# EpromEmu.net
KiCad netlist of a schematic drawn in EAGLE
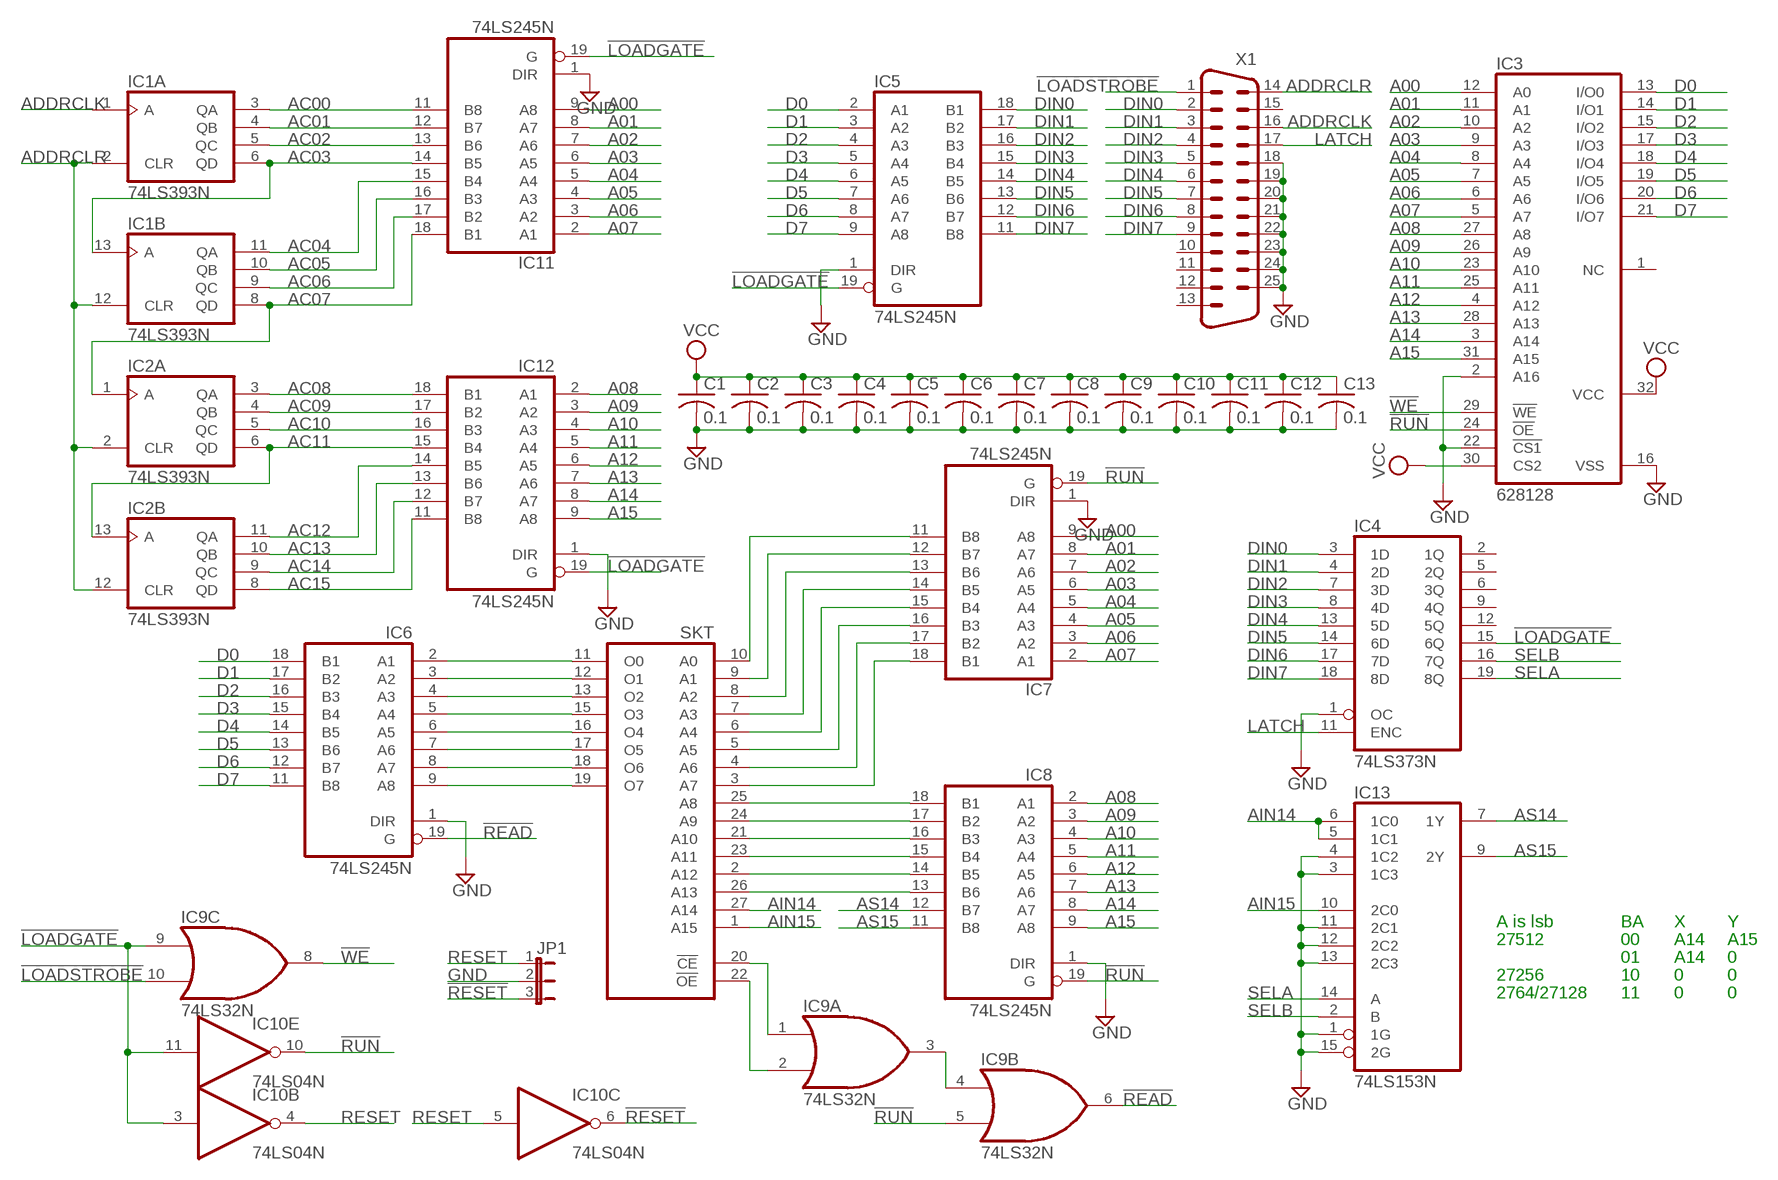
[diagram p0: schematic, sheet 1]

(export (version "E")
  (design (tool "Eeschema 10.0.6"))
  (components
    (comp (ref "C1")
      (value "0.1")
      (footprint "eagle-import:C050-025X075")
      (libsource (lib "eagle-import") (part "C-US050-025X075"))
    )
    (comp (ref "C2")
      (value "0.1")
      (footprint "eagle-import:C050-025X075")
      (libsource (lib "eagle-import") (part "C-US050-025X075"))
    )
    (comp (ref "C3")
      (value "0.1")
      (footprint "eagle-import:C050-025X075")
      (libsource (lib "eagle-import") (part "C-US050-025X075"))
    )
    (comp (ref "C4")
      (value "0.1")
      (footprint "eagle-import:C050-025X075")
      (libsource (lib "eagle-import") (part "C-US050-025X075"))
    )
    (comp (ref "C5")
      (value "0.1")
      (footprint "eagle-import:C050-025X075")
      (libsource (lib "eagle-import") (part "C-US050-025X075"))
    )
    (comp (ref "C6")
      (value "0.1")
      (footprint "eagle-import:C050-025X075")
      (libsource (lib "eagle-import") (part "C-US050-025X075"))
    )
    (comp (ref "C7")
      (value "0.1")
      (footprint "eagle-import:C050-025X075")
      (libsource (lib "eagle-import") (part "C-US050-025X075"))
    )
    (comp (ref "C8")
      (value "0.1")
      (footprint "eagle-import:C050-025X075")
      (libsource (lib "eagle-import") (part "C-US050-025X075"))
    )
    (comp (ref "C9")
      (value "0.1")
      (footprint "eagle-import:C050-025X075")
      (libsource (lib "eagle-import") (part "C-US050-025X075"))
    )
    (comp (ref "C10")
      (value "0.1")
      (footprint "eagle-import:C050-025X075")
      (libsource (lib "eagle-import") (part "C-US050-025X075"))
    )
    (comp (ref "C11")
      (value "0.1")
      (footprint "eagle-import:C050-025X075")
      (libsource (lib "eagle-import") (part "C-US050-025X075"))
    )
    (comp (ref "C12")
      (value "0.1")
      (footprint "eagle-import:C050-025X075")
      (libsource (lib "eagle-import") (part "C-US050-025X075"))
    )
    (comp (ref "C13")
      (value "0.1")
      (footprint "eagle-import:C050-025X075")
      (libsource (lib "eagle-import") (part "C-US050-025X075"))
    )
    (comp (ref "IC1")
      (value "74LS393N")
      (footprint "eagle-import:DIL14")
      (libsource (lib "eagle-import") (part "74393NLS"))
    )
    (comp (ref "IC2")
      (value "74LS393N")
      (footprint "eagle-import:DIL14")
      (libsource (lib "eagle-import") (part "74393NLS"))
    )
    (comp (ref "IC3")
      (value "628128")
      (footprint "eagle-import:DIL32")
      (libsource (lib "eagle-import") (part "628128P"))
    )
    (comp (ref "IC4")
      (value "74LS373N")
      (footprint "eagle-import:DIL20")
      (libsource (lib "eagle-import") (part "74373NLS"))
    )
    (comp (ref "IC5")
      (value "74LS245N")
      (footprint "eagle-import:DIL20")
      (libsource (lib "eagle-import") (part "74245NLS"))
    )
    (comp (ref "IC6")
      (value "74LS245N")
      (footprint "eagle-import:DIL20")
      (libsource (lib "eagle-import") (part "74245NLS"))
    )
    (comp (ref "IC7")
      (value "74LS245N")
      (footprint "eagle-import:DIL20")
      (libsource (lib "eagle-import") (part "74245NLS"))
    )
    (comp (ref "IC8")
      (value "74LS245N")
      (footprint "eagle-import:DIL20")
      (libsource (lib "eagle-import") (part "74245NLS"))
    )
    (comp (ref "IC9")
      (value "74LS32N")
      (footprint "eagle-import:DIL14")
      (libsource (lib "eagle-import") (part "7432NLS"))
    )
    (comp (ref "IC10")
      (value "74LS04N")
      (footprint "eagle-import:DIL14")
      (libsource (lib "eagle-import") (part "7404NLS"))
    )
    (comp (ref "IC11")
      (value "74LS245N")
      (footprint "eagle-import:DIL20")
      (libsource (lib "eagle-import") (part "74245NLS"))
    )
    (comp (ref "IC12")
      (value "74LS245N")
      (footprint "eagle-import:DIL20")
      (libsource (lib "eagle-import") (part "74245NLS"))
    )
    (comp (ref "IC13")
      (value "74LS153N")
      (footprint "eagle-import:DIL16")
      (libsource (lib "eagle-import") (part "74153NLS"))
    )
    (comp (ref "JP1")
      (value "JP2E")
      (footprint "eagle-import:JP2")
      (libsource (lib "eagle-import") (part "JP2E"))
    )
    (comp (ref "SKT")
      (value "27512")
      (footprint "eagle-import:DIL28")
      (libsource (lib "eagle-import") (part "27512"))
    )
    (comp (ref "X1")
      (value "M25HP")
      (footprint "eagle-import:M25HP")
      (libsource (lib "eagle-import") (part "M25HP"))
    )
  )
  (nets
    (net (code "1") (name "/A00") (class "Default")
      (node (ref "IC11") (pin "9") (pinfunction "A8_9") (pintype "bidirectional"))
      (node (ref "IC3") (pin "12") (pinfunction "A0_12") (pintype "input"))
      (node (ref "IC7") (pin "9") (pinfunction "A8_9") (pintype "bidirectional"))
    )
    (net (code "2") (name "/A01") (class "Default")
      (node (ref "IC11") (pin "8") (pinfunction "A7_8") (pintype "bidirectional"))
      (node (ref "IC3") (pin "11") (pinfunction "A1_11") (pintype "input"))
      (node (ref "IC7") (pin "8") (pinfunction "A7_8") (pintype "bidirectional"))
    )
    (net (code "3") (name "/A02") (class "Default")
      (node (ref "IC11") (pin "7") (pinfunction "A6_7") (pintype "bidirectional"))
      (node (ref "IC3") (pin "10") (pinfunction "A2_10") (pintype "input"))
      (node (ref "IC7") (pin "7") (pinfunction "A6_7") (pintype "bidirectional"))
    )
    (net (code "4") (name "/A03") (class "Default")
      (node (ref "IC11") (pin "6") (pinfunction "A5_6") (pintype "bidirectional"))
      (node (ref "IC3") (pin "9") (pinfunction "A3_9") (pintype "input"))
      (node (ref "IC7") (pin "6") (pinfunction "A5_6") (pintype "bidirectional"))
    )
    (net (code "5") (name "/A04") (class "Default")
      (node (ref "IC11") (pin "5") (pinfunction "A4_5") (pintype "bidirectional"))
      (node (ref "IC3") (pin "8") (pinfunction "A4_8") (pintype "input"))
      (node (ref "IC7") (pin "5") (pinfunction "A4_5") (pintype "bidirectional"))
    )
    (net (code "6") (name "/A05") (class "Default")
      (node (ref "IC11") (pin "4") (pinfunction "A3_4") (pintype "bidirectional"))
      (node (ref "IC3") (pin "7") (pinfunction "A5_7") (pintype "input"))
      (node (ref "IC7") (pin "4") (pinfunction "A3_4") (pintype "bidirectional"))
    )
    (net (code "7") (name "/A06") (class "Default")
      (node (ref "IC11") (pin "3") (pinfunction "A2_3") (pintype "bidirectional"))
      (node (ref "IC3") (pin "6") (pinfunction "A6_6") (pintype "input"))
      (node (ref "IC7") (pin "3") (pinfunction "A2_3") (pintype "bidirectional"))
    )
    (net (code "8") (name "/A07") (class "Default")
      (node (ref "IC11") (pin "2") (pinfunction "A1_2") (pintype "bidirectional"))
      (node (ref "IC3") (pin "5") (pinfunction "A7_5") (pintype "input"))
      (node (ref "IC7") (pin "2") (pinfunction "A1_2") (pintype "bidirectional"))
    )
    (net (code "9") (name "/A08") (class "Default")
      (node (ref "IC12") (pin "2") (pinfunction "A1_2") (pintype "bidirectional"))
      (node (ref "IC3") (pin "27") (pinfunction "A8_27") (pintype "input"))
      (node (ref "IC8") (pin "2") (pinfunction "A1_2") (pintype "bidirectional"))
    )
    (net (code "10") (name "/A09") (class "Default")
      (node (ref "IC12") (pin "3") (pinfunction "A2_3") (pintype "bidirectional"))
      (node (ref "IC3") (pin "26") (pinfunction "A9_26") (pintype "input"))
      (node (ref "IC8") (pin "3") (pinfunction "A2_3") (pintype "bidirectional"))
    )
    (net (code "11") (name "/A10") (class "Default")
      (node (ref "IC12") (pin "4") (pinfunction "A3_4") (pintype "bidirectional"))
      (node (ref "IC3") (pin "23") (pinfunction "A10_23") (pintype "input"))
      (node (ref "IC8") (pin "4") (pinfunction "A3_4") (pintype "bidirectional"))
    )
    (net (code "12") (name "/A11") (class "Default")
      (node (ref "IC12") (pin "5") (pinfunction "A4_5") (pintype "bidirectional"))
      (node (ref "IC3") (pin "25") (pinfunction "A11_25") (pintype "input"))
      (node (ref "IC8") (pin "5") (pinfunction "A4_5") (pintype "bidirectional"))
    )
    (net (code "13") (name "/A12") (class "Default")
      (node (ref "IC12") (pin "6") (pinfunction "A5_6") (pintype "bidirectional"))
      (node (ref "IC3") (pin "4") (pinfunction "A12_4") (pintype "input"))
      (node (ref "IC8") (pin "6") (pinfunction "A5_6") (pintype "bidirectional"))
    )
    (net (code "14") (name "/A13") (class "Default")
      (node (ref "IC12") (pin "7") (pinfunction "A6_7") (pintype "bidirectional"))
      (node (ref "IC3") (pin "28") (pinfunction "A13_28") (pintype "input"))
      (node (ref "IC8") (pin "7") (pinfunction "A6_7") (pintype "bidirectional"))
    )
    (net (code "15") (name "/A14") (class "Default")
      (node (ref "IC12") (pin "8") (pinfunction "A7_8") (pintype "bidirectional"))
      (node (ref "IC3") (pin "3") (pinfunction "A14_3") (pintype "input"))
      (node (ref "IC8") (pin "8") (pinfunction "A7_8") (pintype "bidirectional"))
    )
    (net (code "16") (name "/A15") (class "Default")
      (node (ref "IC12") (pin "9") (pinfunction "A8_9") (pintype "bidirectional"))
      (node (ref "IC3") (pin "31") (pinfunction "A15_31") (pintype "input"))
      (node (ref "IC8") (pin "9") (pinfunction "A8_9") (pintype "bidirectional"))
    )
    (net (code "17") (name "/AC00") (class "Default")
      (node (ref "IC1") (pin "3") (pinfunction "QA_3") (pintype "output"))
      (node (ref "IC11") (pin "11") (pinfunction "B8_11") (pintype "bidirectional"))
    )
    (net (code "18") (name "/AC01") (class "Default")
      (node (ref "IC1") (pin "4") (pinfunction "QB_4") (pintype "output"))
      (node (ref "IC11") (pin "12") (pinfunction "B7_12") (pintype "bidirectional"))
    )
    (net (code "19") (name "/AC02") (class "Default")
      (node (ref "IC1") (pin "5") (pinfunction "QC_5") (pintype "output"))
      (node (ref "IC11") (pin "13") (pinfunction "B6_13") (pintype "bidirectional"))
    )
    (net (code "20") (name "/AC03") (class "Default")
      (node (ref "IC1") (pin "13") (pinfunction "A_13") (pintype "input"))
      (node (ref "IC1") (pin "6") (pinfunction "QD_6") (pintype "output"))
      (node (ref "IC11") (pin "14") (pinfunction "B5_14") (pintype "bidirectional"))
    )
    (net (code "21") (name "/AC04") (class "Default")
      (node (ref "IC1") (pin "11") (pinfunction "QA_11") (pintype "output"))
      (node (ref "IC11") (pin "15") (pinfunction "B4_15") (pintype "bidirectional"))
    )
    (net (code "22") (name "/AC05") (class "Default")
      (node (ref "IC1") (pin "10") (pinfunction "QB_10") (pintype "output"))
      (node (ref "IC11") (pin "16") (pinfunction "B3_16") (pintype "bidirectional"))
    )
    (net (code "23") (name "/AC06") (class "Default")
      (node (ref "IC1") (pin "9") (pinfunction "QC_9") (pintype "output"))
      (node (ref "IC11") (pin "17") (pinfunction "B2_17") (pintype "bidirectional"))
    )
    (net (code "24") (name "/AC07") (class "Default")
      (node (ref "IC1") (pin "8") (pinfunction "QD_8") (pintype "output"))
      (node (ref "IC11") (pin "18") (pinfunction "B1_18") (pintype "bidirectional"))
      (node (ref "IC2") (pin "1") (pinfunction "A_1") (pintype "input"))
    )
    (net (code "25") (name "/AC08") (class "Default")
      (node (ref "IC12") (pin "18") (pinfunction "B1_18") (pintype "bidirectional"))
      (node (ref "IC2") (pin "3") (pinfunction "QA_3") (pintype "output"))
    )
    (net (code "26") (name "/AC09") (class "Default")
      (node (ref "IC12") (pin "17") (pinfunction "B2_17") (pintype "bidirectional"))
      (node (ref "IC2") (pin "4") (pinfunction "QB_4") (pintype "output"))
    )
    (net (code "27") (name "/AC10") (class "Default")
      (node (ref "IC12") (pin "16") (pinfunction "B3_16") (pintype "bidirectional"))
      (node (ref "IC2") (pin "5") (pinfunction "QC_5") (pintype "output"))
    )
    (net (code "28") (name "/AC11") (class "Default")
      (node (ref "IC12") (pin "15") (pinfunction "B4_15") (pintype "bidirectional"))
      (node (ref "IC2") (pin "13") (pinfunction "A_13") (pintype "input"))
      (node (ref "IC2") (pin "6") (pinfunction "QD_6") (pintype "output"))
    )
    (net (code "29") (name "/AC12") (class "Default")
      (node (ref "IC12") (pin "14") (pinfunction "B5_14") (pintype "bidirectional"))
      (node (ref "IC2") (pin "11") (pinfunction "QA_11") (pintype "output"))
    )
    (net (code "30") (name "/AC13") (class "Default")
      (node (ref "IC12") (pin "13") (pinfunction "B6_13") (pintype "bidirectional"))
      (node (ref "IC2") (pin "10") (pinfunction "QB_10") (pintype "output"))
    )
    (net (code "31") (name "/AC14") (class "Default")
      (node (ref "IC12") (pin "12") (pinfunction "B7_12") (pintype "bidirectional"))
      (node (ref "IC2") (pin "9") (pinfunction "QC_9") (pintype "output"))
    )
    (net (code "32") (name "/AC15") (class "Default")
      (node (ref "IC12") (pin "11") (pinfunction "B8_11") (pintype "bidirectional"))
      (node (ref "IC2") (pin "8") (pinfunction "QD_8") (pintype "output"))
    )
    (net (code "33") (name "/ADDRCLK") (class "Default")
      (node (ref "IC1") (pin "1") (pinfunction "A_1") (pintype "input"))
      (node (ref "X1") (pin "16") (pinfunction "16_16") (pintype "passive"))
    )
    (net (code "34") (name "/ADDRCLR") (class "Default")
      (node (ref "IC1") (pin "12") (pinfunction "CLR_12") (pintype "input"))
      (node (ref "IC1") (pin "2") (pinfunction "CLR_2") (pintype "input"))
      (node (ref "IC2") (pin "12") (pinfunction "CLR_12") (pintype "input"))
      (node (ref "IC2") (pin "2") (pinfunction "CLR_2") (pintype "input"))
      (node (ref "X1") (pin "14") (pinfunction "14_14") (pintype "passive"))
    )
    (net (code "35") (name "/AIN14") (class "Default")
      (node (ref "IC13") (pin "5") (pinfunction "1C1_5") (pintype "input"))
      (node (ref "IC13") (pin "6") (pinfunction "1C0_6") (pintype "input"))
      (node (ref "SKT") (pin "27") (pinfunction "A14_27") (pintype "input"))
    )
    (net (code "36") (name "/AIN15") (class "Default")
      (node (ref "IC13") (pin "10") (pinfunction "2C0_10") (pintype "input"))
      (node (ref "SKT") (pin "1") (pinfunction "A15_1") (pintype "input"))
    )
    (net (code "37") (name "/AS14") (class "Default")
      (node (ref "IC13") (pin "7") (pinfunction "1Y_7") (pintype "output"))
      (node (ref "IC8") (pin "12") (pinfunction "B7_12") (pintype "bidirectional"))
    )
    (net (code "38") (name "/AS15") (class "Default")
      (node (ref "IC13") (pin "9") (pinfunction "2Y_9") (pintype "output"))
      (node (ref "IC8") (pin "11") (pinfunction "B8_11") (pintype "bidirectional"))
    )
    (net (code "39") (name "/D0") (class "Default")
      (node (ref "IC3") (pin "13") (pinfunction "I/O0_13") (pintype "bidirectional"))
      (node (ref "IC5") (pin "2") (pinfunction "A1_2") (pintype "bidirectional"))
      (node (ref "IC6") (pin "18") (pinfunction "B1_18") (pintype "bidirectional"))
    )
    (net (code "40") (name "/D1") (class "Default")
      (node (ref "IC3") (pin "14") (pinfunction "I/O1_14") (pintype "bidirectional"))
      (node (ref "IC5") (pin "3") (pinfunction "A2_3") (pintype "bidirectional"))
      (node (ref "IC6") (pin "17") (pinfunction "B2_17") (pintype "bidirectional"))
    )
    (net (code "41") (name "/D2") (class "Default")
      (node (ref "IC3") (pin "15") (pinfunction "I/O2_15") (pintype "bidirectional"))
      (node (ref "IC5") (pin "4") (pinfunction "A3_4") (pintype "bidirectional"))
      (node (ref "IC6") (pin "16") (pinfunction "B3_16") (pintype "bidirectional"))
    )
    (net (code "42") (name "/D3") (class "Default")
      (node (ref "IC3") (pin "17") (pinfunction "I/O3_17") (pintype "bidirectional"))
      (node (ref "IC5") (pin "5") (pinfunction "A4_5") (pintype "bidirectional"))
      (node (ref "IC6") (pin "15") (pinfunction "B4_15") (pintype "bidirectional"))
    )
    (net (code "43") (name "/D4") (class "Default")
      (node (ref "IC3") (pin "18") (pinfunction "I/O4_18") (pintype "bidirectional"))
      (node (ref "IC5") (pin "6") (pinfunction "A5_6") (pintype "bidirectional"))
      (node (ref "IC6") (pin "14") (pinfunction "B5_14") (pintype "bidirectional"))
    )
    (net (code "44") (name "/D5") (class "Default")
      (node (ref "IC3") (pin "19") (pinfunction "I/O5_19") (pintype "bidirectional"))
      (node (ref "IC5") (pin "7") (pinfunction "A6_7") (pintype "bidirectional"))
      (node (ref "IC6") (pin "13") (pinfunction "B6_13") (pintype "bidirectional"))
    )
    (net (code "45") (name "/D6") (class "Default")
      (node (ref "IC3") (pin "20") (pinfunction "I/O6_20") (pintype "bidirectional"))
      (node (ref "IC5") (pin "8") (pinfunction "A7_8") (pintype "bidirectional"))
      (node (ref "IC6") (pin "12") (pinfunction "B7_12") (pintype "bidirectional"))
    )
    (net (code "46") (name "/D7") (class "Default")
      (node (ref "IC3") (pin "21") (pinfunction "I/O7_21") (pintype "bidirectional"))
      (node (ref "IC5") (pin "9") (pinfunction "A8_9") (pintype "bidirectional"))
      (node (ref "IC6") (pin "11") (pinfunction "B8_11") (pintype "bidirectional"))
    )
    (net (code "47") (name "/DIN0") (class "Default")
      (node (ref "IC4") (pin "3") (pinfunction "1D_3") (pintype "input"))
      (node (ref "IC5") (pin "18") (pinfunction "B1_18") (pintype "bidirectional"))
      (node (ref "X1") (pin "2") (pinfunction "2_2") (pintype "passive"))
    )
    (net (code "48") (name "/DIN1") (class "Default")
      (node (ref "IC4") (pin "4") (pinfunction "2D_4") (pintype "input"))
      (node (ref "IC5") (pin "17") (pinfunction "B2_17") (pintype "bidirectional"))
      (node (ref "X1") (pin "3") (pinfunction "3_3") (pintype "passive"))
    )
    (net (code "49") (name "/DIN2") (class "Default")
      (node (ref "IC4") (pin "7") (pinfunction "3D_7") (pintype "input"))
      (node (ref "IC5") (pin "16") (pinfunction "B3_16") (pintype "bidirectional"))
      (node (ref "X1") (pin "4") (pinfunction "4_4") (pintype "passive"))
    )
    (net (code "50") (name "/DIN3") (class "Default")
      (node (ref "IC4") (pin "8") (pinfunction "4D_8") (pintype "input"))
      (node (ref "IC5") (pin "15") (pinfunction "B4_15") (pintype "bidirectional"))
      (node (ref "X1") (pin "5") (pinfunction "5_5") (pintype "passive"))
    )
    (net (code "51") (name "/DIN4") (class "Default")
      (node (ref "IC4") (pin "13") (pinfunction "5D_13") (pintype "input"))
      (node (ref "IC5") (pin "14") (pinfunction "B5_14") (pintype "bidirectional"))
      (node (ref "X1") (pin "6") (pinfunction "6_6") (pintype "passive"))
    )
    (net (code "52") (name "/DIN5") (class "Default")
      (node (ref "IC4") (pin "14") (pinfunction "6D_14") (pintype "input"))
      (node (ref "IC5") (pin "13") (pinfunction "B6_13") (pintype "bidirectional"))
      (node (ref "X1") (pin "7") (pinfunction "7_7") (pintype "passive"))
    )
    (net (code "53") (name "/DIN6") (class "Default")
      (node (ref "IC4") (pin "17") (pinfunction "7D_17") (pintype "input"))
      (node (ref "IC5") (pin "12") (pinfunction "B7_12") (pintype "bidirectional"))
      (node (ref "X1") (pin "8") (pinfunction "8_8") (pintype "passive"))
    )
    (net (code "54") (name "/DIN7") (class "Default")
      (node (ref "IC4") (pin "18") (pinfunction "8D_18") (pintype "input"))
      (node (ref "IC5") (pin "11") (pinfunction "B8_11") (pintype "bidirectional"))
      (node (ref "X1") (pin "9") (pinfunction "9_9") (pintype "passive"))
    )
    (net (code "55") (name "/LATCH") (class "Default")
      (node (ref "IC4") (pin "11") (pinfunction "ENC_11") (pintype "input"))
      (node (ref "X1") (pin "17") (pinfunction "17_17") (pintype "passive"))
    )
    (net (code "56") (name "/RESET") (class "Default")
      (node (ref "IC10") (pin "4") (pinfunction "O_4") (pintype "output"))
      (node (ref "IC10") (pin "5") (pinfunction "I_5") (pintype "input"))
      (node (ref "JP1") (pin "1") (pinfunction "1_1") (pintype "passive"))
    )
    (net (code "57") (name "/SELA") (class "Default")
      (node (ref "IC13") (pin "14") (pinfunction "A_14") (pintype "input"))
      (node (ref "IC4") (pin "19") (pinfunction "8Q_19") (pintype "tri_state"))
    )
    (net (code "58") (name "/SELB") (class "Default")
      (node (ref "IC13") (pin "2") (pinfunction "B_2") (pintype "input"))
      (node (ref "IC4") (pin "16") (pinfunction "7Q_16") (pintype "tri_state"))
    )
    (net (code "59") (name "/~{LOADGATE}") (class "Default")
      (node (ref "IC10") (pin "11") (pinfunction "I_11") (pintype "input"))
      (node (ref "IC10") (pin "3") (pinfunction "I_3") (pintype "input"))
      (node (ref "IC11") (pin "19") (pinfunction "G_19") (pintype "input"))
      (node (ref "IC12") (pin "19") (pinfunction "G_19") (pintype "input"))
      (node (ref "IC4") (pin "15") (pinfunction "6Q_15") (pintype "tri_state"))
      (node (ref "IC5") (pin "19") (pinfunction "G_19") (pintype "input"))
      (node (ref "IC9") (pin "9") (pinfunction "I0_9") (pintype "input"))
    )
    (net (code "60") (name "/~{LOADSTROBE}") (class "Default")
      (node (ref "IC9") (pin "10") (pinfunction "I1_10") (pintype "input"))
      (node (ref "X1") (pin "1") (pinfunction "1_1") (pintype "passive"))
    )
    (net (code "61") (name "/~{READ}") (class "Default")
      (node (ref "IC6") (pin "19") (pinfunction "G_19") (pintype "input"))
      (node (ref "IC9") (pin "6") (pinfunction "O_6") (pintype "output"))
    )
    (net (code "62") (name "/~{RESET}") (class "Default")
      (node (ref "IC10") (pin "6") (pinfunction "O_6") (pintype "output"))
      (node (ref "JP1") (pin "3") (pinfunction "3_3") (pintype "passive"))
    )
    (net (code "63") (name "/~{RUN}") (class "Default")
      (node (ref "IC10") (pin "10") (pinfunction "O_10") (pintype "output"))
      (node (ref "IC3") (pin "24") (pinfunction "~{OE}_24") (pintype "input"))
      (node (ref "IC7") (pin "19") (pinfunction "G_19") (pintype "input"))
      (node (ref "IC8") (pin "19") (pinfunction "G_19") (pintype "input"))
      (node (ref "IC9") (pin "5") (pinfunction "I1_5") (pintype "input"))
    )
    (net (code "64") (name "/~{WE}") (class "Default")
      (node (ref "IC3") (pin "29") (pinfunction "~{WE}_29") (pintype "input"))
      (node (ref "IC9") (pin "8") (pinfunction "O_8") (pintype "output"))
    )
    (net (code "65") (name "GND") (class "Default")
      (node (ref "C1") (pin "2") (pinfunction "2_2") (pintype "passive"))
      (node (ref "C10") (pin "2") (pinfunction "2_2") (pintype "passive"))
      (node (ref "C11") (pin "2") (pinfunction "2_2") (pintype "passive"))
      (node (ref "C12") (pin "2") (pinfunction "2_2") (pintype "passive"))
      (node (ref "C13") (pin "2") (pinfunction "2_2") (pintype "passive"))
      (node (ref "C2") (pin "2") (pinfunction "2_2") (pintype "passive"))
      (node (ref "C3") (pin "2") (pinfunction "2_2") (pintype "passive"))
      (node (ref "C4") (pin "2") (pinfunction "2_2") (pintype "passive"))
      (node (ref "C5") (pin "2") (pinfunction "2_2") (pintype "passive"))
      (node (ref "C6") (pin "2") (pinfunction "2_2") (pintype "passive"))
      (node (ref "C7") (pin "2") (pinfunction "2_2") (pintype "passive"))
      (node (ref "C8") (pin "2") (pinfunction "2_2") (pintype "passive"))
      (node (ref "C9") (pin "2") (pinfunction "2_2") (pintype "passive"))
      (node (ref "IC11") (pin "1") (pinfunction "DIR_1") (pintype "input"))
      (node (ref "IC12") (pin "1") (pinfunction "DIR_1") (pintype "input"))
      (node (ref "IC13") (pin "1") (pinfunction "1G_1") (pintype "input"))
      (node (ref "IC13") (pin "11") (pinfunction "2C1_11") (pintype "input"))
      (node (ref "IC13") (pin "12") (pinfunction "2C2_12") (pintype "input"))
      (node (ref "IC13") (pin "13") (pinfunction "2C3_13") (pintype "input"))
      (node (ref "IC13") (pin "15") (pinfunction "2G_15") (pintype "input"))
      (node (ref "IC13") (pin "3") (pinfunction "1C3_3") (pintype "input"))
      (node (ref "IC13") (pin "4") (pinfunction "1C2_4") (pintype "input"))
      (node (ref "IC3") (pin "16") (pinfunction "VSS_16") (pintype "power_in"))
      (node (ref "IC3") (pin "2") (pinfunction "A16_2") (pintype "input"))
      (node (ref "IC3") (pin "22") (pinfunction "~{CS1}_22") (pintype "input"))
      (node (ref "IC4") (pin "1") (pinfunction "OC_1") (pintype "input"))
      (node (ref "IC5") (pin "1") (pinfunction "DIR_1") (pintype "input"))
      (node (ref "IC6") (pin "1") (pinfunction "DIR_1") (pintype "input"))
      (node (ref "IC7") (pin "1") (pinfunction "DIR_1") (pintype "input"))
      (node (ref "IC8") (pin "1") (pinfunction "DIR_1") (pintype "input"))
      (node (ref "JP1") (pin "2") (pinfunction "2_2") (pintype "passive"))
      (node (ref "X1") (pin "18") (pinfunction "18_18") (pintype "passive"))
      (node (ref "X1") (pin "19") (pinfunction "19_19") (pintype "passive"))
      (node (ref "X1") (pin "20") (pinfunction "20_20") (pintype "passive"))
      (node (ref "X1") (pin "21") (pinfunction "21_21") (pintype "passive"))
      (node (ref "X1") (pin "22") (pinfunction "22_22") (pintype "passive"))
      (node (ref "X1") (pin "23") (pinfunction "23_23") (pintype "passive"))
      (node (ref "X1") (pin "24") (pinfunction "24_24") (pintype "passive"))
      (node (ref "X1") (pin "25") (pinfunction "25_25") (pintype "passive"))
    )
    (net (code "66") (name "Net-(IC6A-A1)") (class "Default")
      (node (ref "IC6") (pin "2") (pinfunction "A1_2") (pintype "bidirectional"))
      (node (ref "SKT") (pin "11") (pinfunction "O0_11") (pintype "tri_state"))
    )
    (net (code "67") (name "Net-(IC6A-A2)") (class "Default")
      (node (ref "IC6") (pin "3") (pinfunction "A2_3") (pintype "bidirectional"))
      (node (ref "SKT") (pin "12") (pinfunction "O1_12") (pintype "tri_state"))
    )
    (net (code "68") (name "Net-(IC6A-A3)") (class "Default")
      (node (ref "IC6") (pin "4") (pinfunction "A3_4") (pintype "bidirectional"))
      (node (ref "SKT") (pin "13") (pinfunction "O2_13") (pintype "tri_state"))
    )
    (net (code "69") (name "Net-(IC6A-A4)") (class "Default")
      (node (ref "IC6") (pin "5") (pinfunction "A4_5") (pintype "bidirectional"))
      (node (ref "SKT") (pin "15") (pinfunction "O3_15") (pintype "tri_state"))
    )
    (net (code "70") (name "Net-(IC6A-A5)") (class "Default")
      (node (ref "IC6") (pin "6") (pinfunction "A5_6") (pintype "bidirectional"))
      (node (ref "SKT") (pin "16") (pinfunction "O4_16") (pintype "tri_state"))
    )
    (net (code "71") (name "Net-(IC6A-A6)") (class "Default")
      (node (ref "IC6") (pin "7") (pinfunction "A6_7") (pintype "bidirectional"))
      (node (ref "SKT") (pin "17") (pinfunction "O5_17") (pintype "tri_state"))
    )
    (net (code "72") (name "Net-(IC6A-A7)") (class "Default")
      (node (ref "IC6") (pin "8") (pinfunction "A7_8") (pintype "bidirectional"))
      (node (ref "SKT") (pin "18") (pinfunction "O6_18") (pintype "tri_state"))
    )
    (net (code "73") (name "Net-(IC6A-A8)") (class "Default")
      (node (ref "IC6") (pin "9") (pinfunction "A8_9") (pintype "bidirectional"))
      (node (ref "SKT") (pin "19") (pinfunction "O7_19") (pintype "tri_state"))
    )
    (net (code "74") (name "Net-(IC7A-B1)") (class "Default")
      (node (ref "IC7") (pin "18") (pinfunction "B1_18") (pintype "bidirectional"))
      (node (ref "SKT") (pin "3") (pinfunction "A7_3") (pintype "input"))
    )
    (net (code "75") (name "Net-(IC7A-B2)") (class "Default")
      (node (ref "IC7") (pin "17") (pinfunction "B2_17") (pintype "bidirectional"))
      (node (ref "SKT") (pin "4") (pinfunction "A6_4") (pintype "input"))
    )
    (net (code "76") (name "Net-(IC7A-B3)") (class "Default")
      (node (ref "IC7") (pin "16") (pinfunction "B3_16") (pintype "bidirectional"))
      (node (ref "SKT") (pin "5") (pinfunction "A5_5") (pintype "input"))
    )
    (net (code "77") (name "Net-(IC7A-B4)") (class "Default")
      (node (ref "IC7") (pin "15") (pinfunction "B4_15") (pintype "bidirectional"))
      (node (ref "SKT") (pin "6") (pinfunction "A4_6") (pintype "input"))
    )
    (net (code "78") (name "Net-(IC7A-B5)") (class "Default")
      (node (ref "IC7") (pin "14") (pinfunction "B5_14") (pintype "bidirectional"))
      (node (ref "SKT") (pin "7") (pinfunction "A3_7") (pintype "input"))
    )
    (net (code "79") (name "Net-(IC7A-B6)") (class "Default")
      (node (ref "IC7") (pin "13") (pinfunction "B6_13") (pintype "bidirectional"))
      (node (ref "SKT") (pin "8") (pinfunction "A2_8") (pintype "input"))
    )
    (net (code "80") (name "Net-(IC7A-B7)") (class "Default")
      (node (ref "IC7") (pin "12") (pinfunction "B7_12") (pintype "bidirectional"))
      (node (ref "SKT") (pin "9") (pinfunction "A1_9") (pintype "input"))
    )
    (net (code "81") (name "Net-(IC7A-B8)") (class "Default")
      (node (ref "IC7") (pin "11") (pinfunction "B8_11") (pintype "bidirectional"))
      (node (ref "SKT") (pin "10") (pinfunction "A0_10") (pintype "input"))
    )
    (net (code "82") (name "Net-(IC8A-B1)") (class "Default")
      (node (ref "IC8") (pin "18") (pinfunction "B1_18") (pintype "bidirectional"))
      (node (ref "SKT") (pin "25") (pinfunction "A8_25") (pintype "input"))
    )
    (net (code "83") (name "Net-(IC8A-B2)") (class "Default")
      (node (ref "IC8") (pin "17") (pinfunction "B2_17") (pintype "bidirectional"))
      (node (ref "SKT") (pin "24") (pinfunction "A9_24") (pintype "input"))
    )
    (net (code "84") (name "Net-(IC8A-B3)") (class "Default")
      (node (ref "IC8") (pin "16") (pinfunction "B3_16") (pintype "bidirectional"))
      (node (ref "SKT") (pin "21") (pinfunction "A10_21") (pintype "input"))
    )
    (net (code "85") (name "Net-(IC8A-B4)") (class "Default")
      (node (ref "IC8") (pin "15") (pinfunction "B4_15") (pintype "bidirectional"))
      (node (ref "SKT") (pin "23") (pinfunction "A11_23") (pintype "input"))
    )
    (net (code "86") (name "Net-(IC8A-B5)") (class "Default")
      (node (ref "IC8") (pin "14") (pinfunction "B5_14") (pintype "bidirectional"))
      (node (ref "SKT") (pin "2") (pinfunction "A12_2") (pintype "input"))
    )
    (net (code "87") (name "Net-(IC8A-B6)") (class "Default")
      (node (ref "IC8") (pin "13") (pinfunction "B6_13") (pintype "bidirectional"))
      (node (ref "SKT") (pin "26") (pinfunction "A13_26") (pintype "input"))
    )
    (net (code "88") (name "Net-(IC9A-I0)") (class "Default")
      (node (ref "IC9") (pin "1") (pinfunction "I0_1") (pintype "input"))
      (node (ref "SKT") (pin "20") (pinfunction "~{CE}_20") (pintype "input"))
    )
    (net (code "89") (name "Net-(IC9A-I1)") (class "Default")
      (node (ref "IC9") (pin "2") (pinfunction "I1_2") (pintype "input"))
      (node (ref "SKT") (pin "22") (pinfunction "~{OE}_22") (pintype "input"))
    )
    (net (code "90") (name "Net-(IC9A-O)") (class "Default")
      (node (ref "IC9") (pin "3") (pinfunction "O_3") (pintype "output"))
      (node (ref "IC9") (pin "4") (pinfunction "I0_4") (pintype "input"))
    )
    (net (code "91") (name "VCC") (class "Default")
      (node (ref "C1") (pin "1") (pinfunction "1_1") (pintype "passive"))
      (node (ref "C10") (pin "1") (pinfunction "1_1") (pintype "passive"))
      (node (ref "C11") (pin "1") (pinfunction "1_1") (pintype "passive"))
      (node (ref "C12") (pin "1") (pinfunction "1_1") (pintype "passive"))
      (node (ref "C13") (pin "1") (pinfunction "1_1") (pintype "passive"))
      (node (ref "C2") (pin "1") (pinfunction "1_1") (pintype "passive"))
      (node (ref "C3") (pin "1") (pinfunction "1_1") (pintype "passive"))
      (node (ref "C4") (pin "1") (pinfunction "1_1") (pintype "passive"))
      (node (ref "C5") (pin "1") (pinfunction "1_1") (pintype "passive"))
      (node (ref "C6") (pin "1") (pinfunction "1_1") (pintype "passive"))
      (node (ref "C7") (pin "1") (pinfunction "1_1") (pintype "passive"))
      (node (ref "C8") (pin "1") (pinfunction "1_1") (pintype "passive"))
      (node (ref "C9") (pin "1") (pinfunction "1_1") (pintype "passive"))
      (node (ref "IC3") (pin "30") (pinfunction "CS2_30") (pintype "input"))
      (node (ref "IC3") (pin "32") (pinfunction "VCC_32") (pintype "power_in"))
    )
    (net (code "92") (name "unconnected-(IC3-NC-Pad1)") (class "Default")
      (node (ref "IC3") (pin "1") (pinfunction "NC_1") (pintype "no_connect"))
    )
    (net (code "93") (name "unconnected-(IC4A-1Q-Pad2)") (class "Default")
      (node (ref "IC4") (pin "2") (pinfunction "1Q_2") (pintype "tri_state"))
    )
    (net (code "94") (name "unconnected-(IC4A-2Q-Pad5)") (class "Default")
      (node (ref "IC4") (pin "5") (pinfunction "2Q_5") (pintype "tri_state"))
    )
    (net (code "95") (name "unconnected-(IC4A-3Q-Pad6)") (class "Default")
      (node (ref "IC4") (pin "6") (pinfunction "3Q_6") (pintype "tri_state"))
    )
    (net (code "96") (name "unconnected-(IC4A-4Q-Pad9)") (class "Default")
      (node (ref "IC4") (pin "9") (pinfunction "4Q_9") (pintype "tri_state"))
    )
    (net (code "97") (name "unconnected-(IC4A-5Q-Pad12)") (class "Default")
      (node (ref "IC4") (pin "12") (pinfunction "5Q_12") (pintype "tri_state"))
    )
    (net (code "98") (name "unconnected-(X1-Pad10)") (class "Default")
      (node (ref "X1") (pin "10") (pinfunction "10_10") (pintype "passive"))
    )
    (net (code "99") (name "unconnected-(X1-Pad11)") (class "Default")
      (node (ref "X1") (pin "11") (pinfunction "11_11") (pintype "passive"))
    )
    (net (code "100") (name "unconnected-(X1-Pad12)") (class "Default")
      (node (ref "X1") (pin "12") (pinfunction "12_12") (pintype "passive"))
    )
    (net (code "101") (name "unconnected-(X1-Pad13)") (class "Default")
      (node (ref "X1") (pin "13") (pinfunction "13_13") (pintype "passive"))
    )
    (net (code "102") (name "unconnected-(X1-Pad15)") (class "Default")
      (node (ref "X1") (pin "15") (pinfunction "15_15") (pintype "passive"))
    )
  )
)
